# 1-Schematic_monitoring_v0_1.net
KiCad netlist of a schematic drawn in EasyEDA
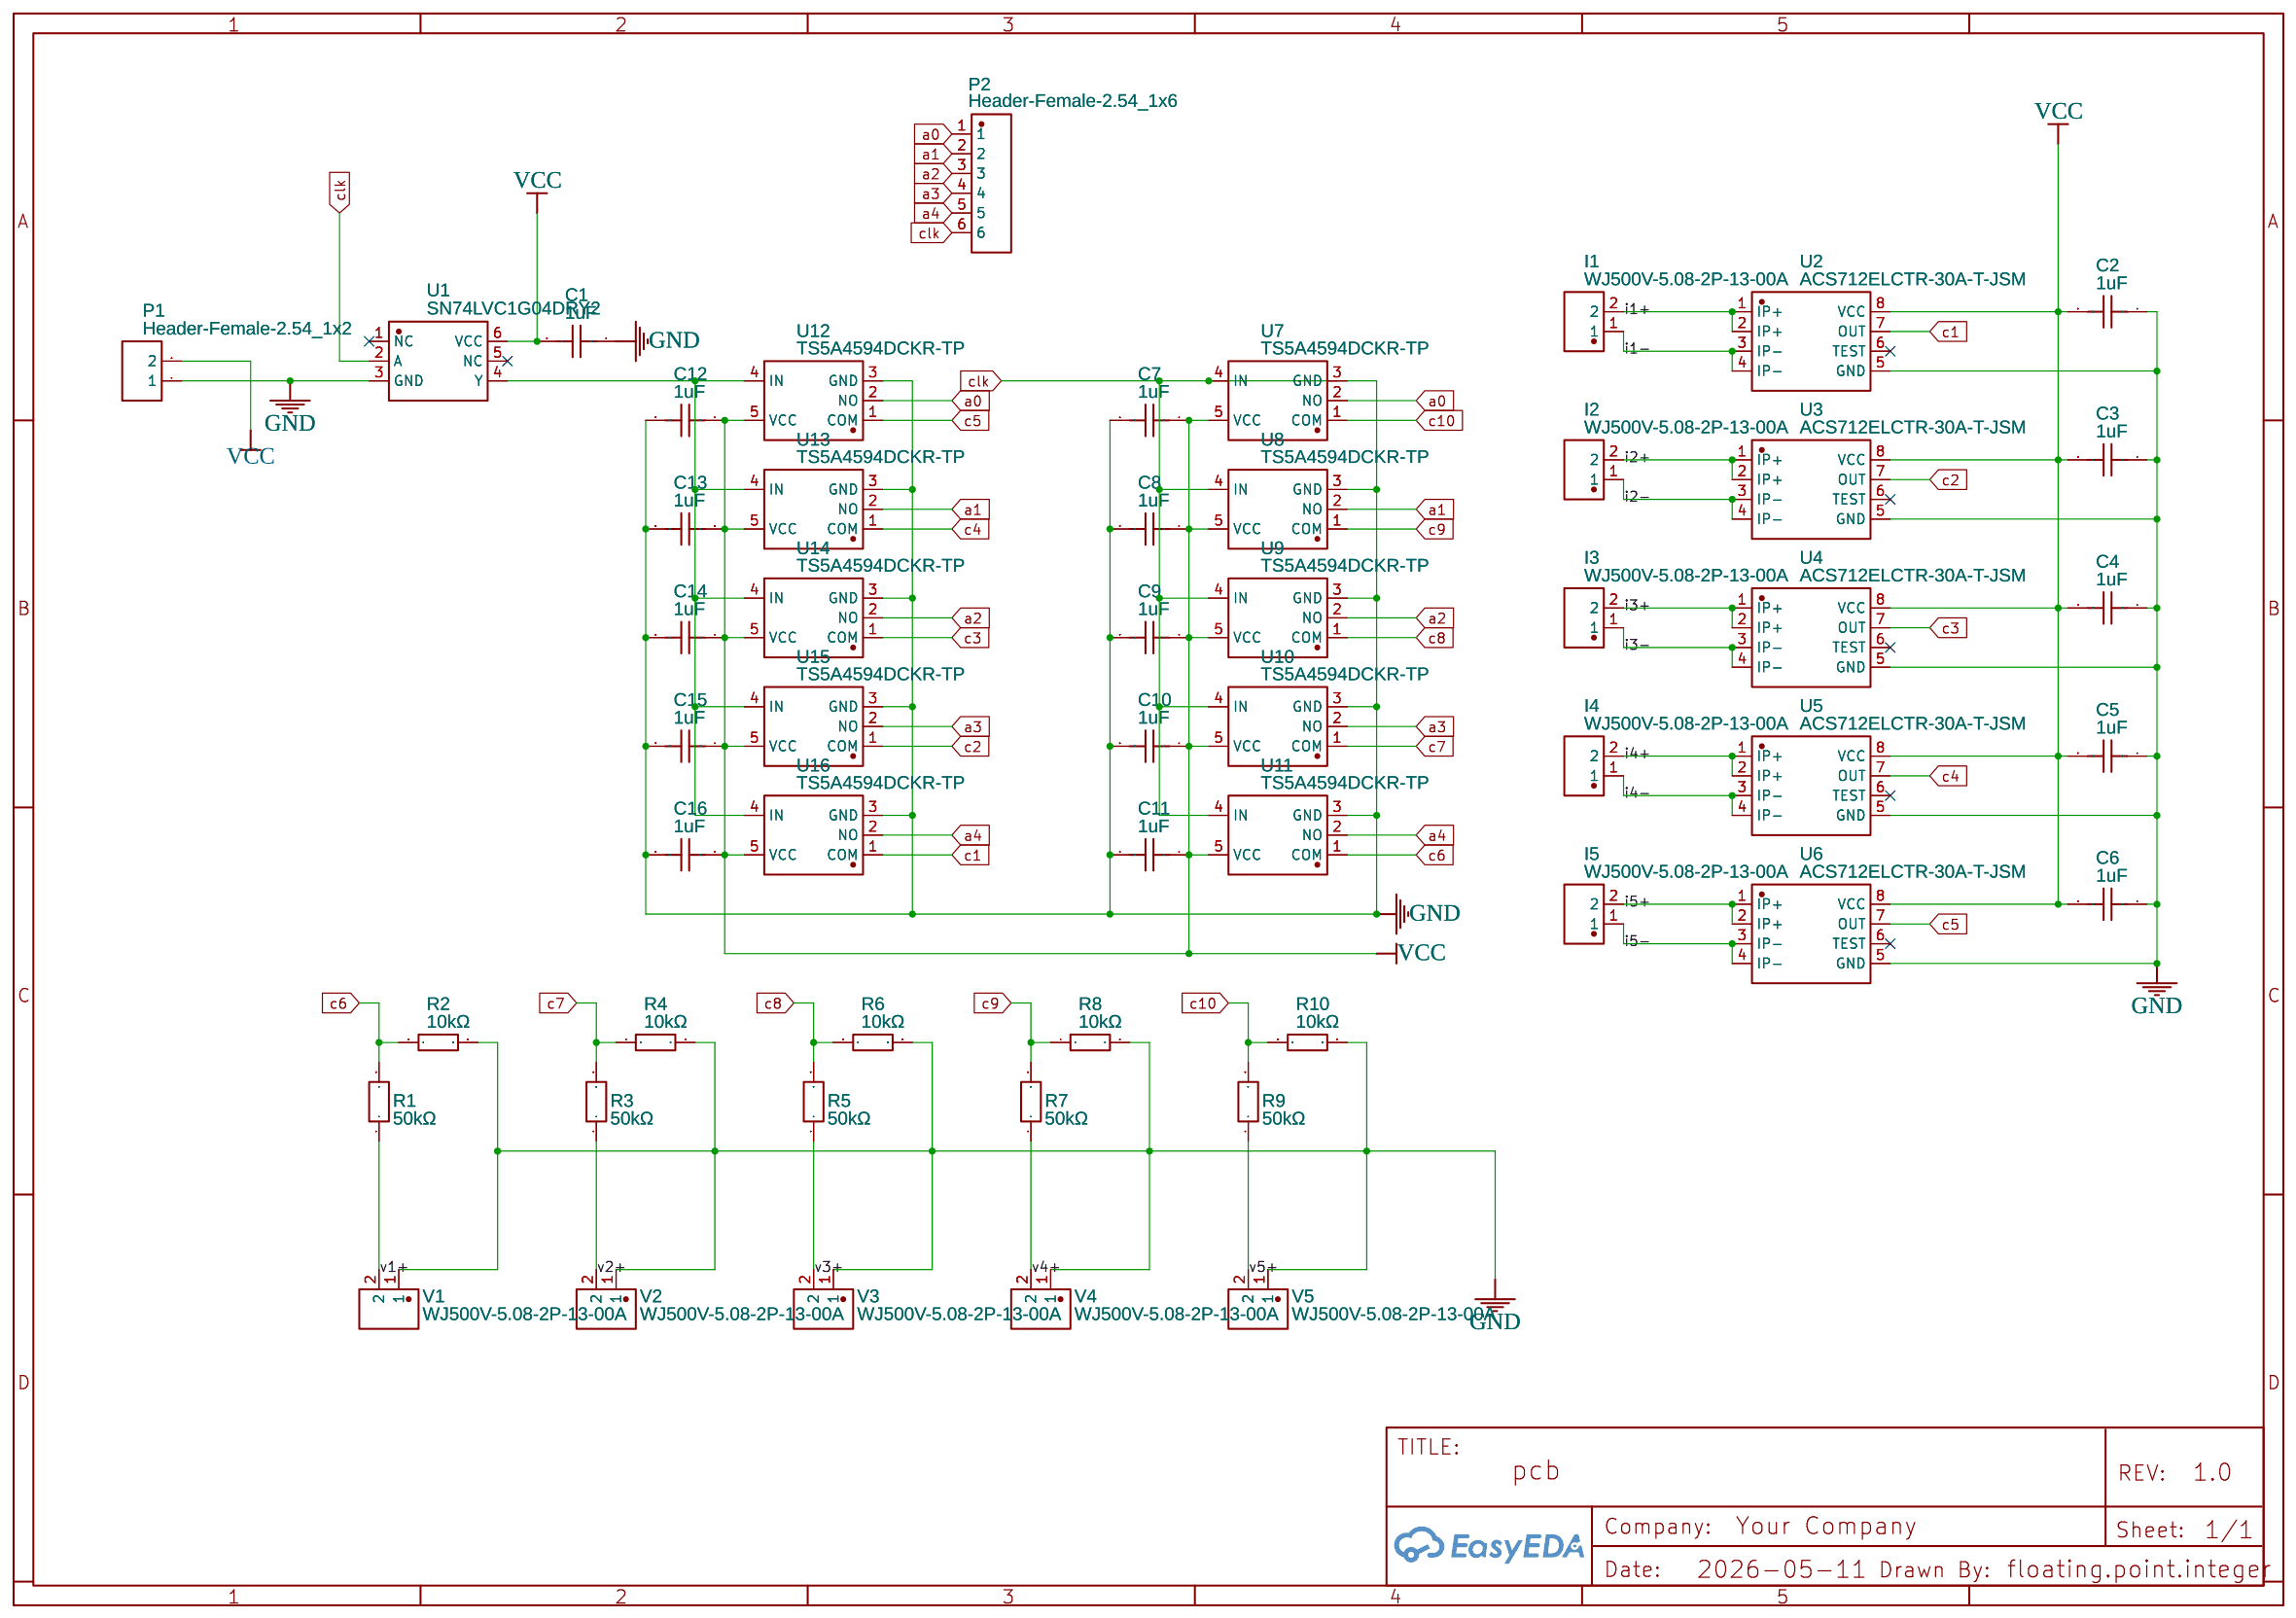
[diagram p0: schematic sheet]

(export (version "E")
  (design (tool "Eeschema 10.0.6"))
  (components
    (comp (ref "C1")
      (value "1uF")
      (fields (field (name "Manufacturer Part") "0603B105K250CT") (field (name "Manufacturer") "Walsin(华新科)"))
      (libsource (lib "") (part "0603B105K250CT"))
    )
    (comp (ref "C2")
      (value "1uF")
      (fields (field (name "Manufacturer Part") "0603B105K250CT") (field (name "Manufacturer") "Walsin(华新科)"))
      (libsource (lib "") (part "0603B105K250CT"))
    )
    (comp (ref "C3")
      (value "1uF")
      (fields (field (name "Manufacturer Part") "0603B105K250CT") (field (name "Manufacturer") "Walsin(华新科)"))
      (libsource (lib "") (part "0603B105K250CT"))
    )
    (comp (ref "C4")
      (value "1uF")
      (fields (field (name "Manufacturer Part") "0603B105K250CT") (field (name "Manufacturer") "Walsin(华新科)"))
      (libsource (lib "") (part "0603B105K250CT"))
    )
    (comp (ref "C5")
      (value "1uF")
      (fields (field (name "Manufacturer Part") "0603B105K250CT") (field (name "Manufacturer") "Walsin(华新科)"))
      (libsource (lib "") (part "0603B105K250CT"))
    )
    (comp (ref "C6")
      (value "1uF")
      (fields (field (name "Manufacturer Part") "0603B105K250CT") (field (name "Manufacturer") "Walsin(华新科)"))
      (libsource (lib "") (part "0603B105K250CT"))
    )
    (comp (ref "C7")
      (value "1uF")
      (fields (field (name "Manufacturer Part") "0603B105K250CT") (field (name "Manufacturer") "Walsin(华新科)"))
      (libsource (lib "") (part "0603B105K250CT"))
    )
    (comp (ref "C8")
      (value "1uF")
      (fields (field (name "Manufacturer Part") "0603B105K250CT") (field (name "Manufacturer") "Walsin(华新科)"))
      (libsource (lib "") (part "0603B105K250CT"))
    )
    (comp (ref "C9")
      (value "1uF")
      (fields (field (name "Manufacturer Part") "0603B105K250CT") (field (name "Manufacturer") "Walsin(华新科)"))
      (libsource (lib "") (part "0603B105K250CT"))
    )
    (comp (ref "C10")
      (value "1uF")
      (fields (field (name "Manufacturer Part") "0603B105K250CT") (field (name "Manufacturer") "Walsin(华新科)"))
      (libsource (lib "") (part "0603B105K250CT"))
    )
    (comp (ref "C11")
      (value "1uF")
      (fields (field (name "Manufacturer Part") "0603B105K250CT") (field (name "Manufacturer") "Walsin(华新科)"))
      (libsource (lib "") (part "0603B105K250CT"))
    )
    (comp (ref "C12")
      (value "1uF")
      (fields (field (name "Manufacturer Part") "0603B105K250CT") (field (name "Manufacturer") "Walsin(华新科)"))
      (libsource (lib "") (part "0603B105K250CT"))
    )
    (comp (ref "C13")
      (value "1uF")
      (fields (field (name "Manufacturer Part") "0603B105K250CT") (field (name "Manufacturer") "Walsin(华新科)"))
      (libsource (lib "") (part "0603B105K250CT"))
    )
    (comp (ref "C14")
      (value "1uF")
      (fields (field (name "Manufacturer Part") "0603B105K250CT") (field (name "Manufacturer") "Walsin(华新科)"))
      (libsource (lib "") (part "0603B105K250CT"))
    )
    (comp (ref "C15")
      (value "1uF")
      (fields (field (name "Manufacturer Part") "0603B105K250CT") (field (name "Manufacturer") "Walsin(华新科)"))
      (libsource (lib "") (part "0603B105K250CT"))
    )
    (comp (ref "C16")
      (value "1uF")
      (fields (field (name "Manufacturer Part") "0603B105K250CT") (field (name "Manufacturer") "Walsin(华新科)"))
      (libsource (lib "") (part "0603B105K250CT"))
    )
    (comp (ref "I1")
      (value "WJ500V-5.08-2P-13-00A")
      (fields
        (field (name "Manufacturer Part") "WJ500V-5.08-02P-13-00A")
        (field (name "Manufacturer") "KANGNEX(康奈克斯电气)")
      )
      (libsource (lib "") (part "WJ500V-5.08-2P-13-00A_1"))
    )
    (comp (ref "I2")
      (value "WJ500V-5.08-2P-13-00A")
      (fields
        (field (name "Manufacturer Part") "WJ500V-5.08-02P-13-00A")
        (field (name "Manufacturer") "KANGNEX(康奈克斯电气)")
      )
      (libsource (lib "") (part "WJ500V-5.08-2P-13-00A_1"))
    )
    (comp (ref "I3")
      (value "WJ500V-5.08-2P-13-00A")
      (fields
        (field (name "Manufacturer Part") "WJ500V-5.08-02P-13-00A")
        (field (name "Manufacturer") "KANGNEX(康奈克斯电气)")
      )
      (libsource (lib "") (part "WJ500V-5.08-2P-13-00A_1"))
    )
    (comp (ref "I4")
      (value "WJ500V-5.08-2P-13-00A")
      (fields
        (field (name "Manufacturer Part") "WJ500V-5.08-02P-13-00A")
        (field (name "Manufacturer") "KANGNEX(康奈克斯电气)")
      )
      (libsource (lib "") (part "WJ500V-5.08-2P-13-00A_1"))
    )
    (comp (ref "I5")
      (value "WJ500V-5.08-2P-13-00A")
      (fields
        (field (name "Manufacturer Part") "WJ500V-5.08-02P-13-00A")
        (field (name "Manufacturer") "KANGNEX(康奈克斯电气)")
      )
      (libsource (lib "") (part "WJ500V-5.08-2P-13-00A_1"))
    )
    (comp (ref "P1")
      (value "Header-Female-2.54_1x2")
      (fields (field (name "Manufacturer Part") "2.54-1*2P母") (field (name "Manufacturer") "BOOMELE(博穆精密)"))
      (libsource (lib "") (part "Header-Female-2.54_1x2"))
    )
    (comp (ref "P2")
      (value "Header-Female-2.54_1x6")
      (fields (field (name "Manufacturer Part") "2.54-1*6P母") (field (name "Manufacturer") "BOOMELE(博穆精密)"))
      (libsource (lib "") (part "Header-Female-2.54_1x6"))
    )
    (comp (ref "R1")
      (value "50kΩ")
      (fields (field (name "Manufacturer Part") "RT0603BRD0750KL") (field (name "Manufacturer") "YAGEO(国巨)"))
      (libsource (lib "") (part "RT0603BRD0750KL"))
    )
    (comp (ref "R2")
      (value "10kΩ")
      (fields (field (name "Manufacturer Part") "RT0603DRD0710KL") (field (name "Manufacturer") "YAGEO(国巨)"))
      (libsource (lib "") (part "RT0603DRD0710KL"))
    )
    (comp (ref "R3")
      (value "50kΩ")
      (fields (field (name "Manufacturer Part") "RT0603BRD0750KL") (field (name "Manufacturer") "YAGEO(国巨)"))
      (libsource (lib "") (part "RT0603BRD0750KL"))
    )
    (comp (ref "R4")
      (value "10kΩ")
      (fields (field (name "Manufacturer Part") "RT0603DRD0710KL") (field (name "Manufacturer") "YAGEO(国巨)"))
      (libsource (lib "") (part "RT0603DRD0710KL"))
    )
    (comp (ref "R5")
      (value "50kΩ")
      (fields (field (name "Manufacturer Part") "RT0603BRD0750KL") (field (name "Manufacturer") "YAGEO(国巨)"))
      (libsource (lib "") (part "RT0603BRD0750KL"))
    )
    (comp (ref "R6")
      (value "10kΩ")
      (fields (field (name "Manufacturer Part") "RT0603DRD0710KL") (field (name "Manufacturer") "YAGEO(国巨)"))
      (libsource (lib "") (part "RT0603DRD0710KL"))
    )
    (comp (ref "R7")
      (value "50kΩ")
      (fields (field (name "Manufacturer Part") "RT0603BRD0750KL") (field (name "Manufacturer") "YAGEO(国巨)"))
      (libsource (lib "") (part "RT0603BRD0750KL"))
    )
    (comp (ref "R8")
      (value "10kΩ")
      (fields (field (name "Manufacturer Part") "RT0603DRD0710KL") (field (name "Manufacturer") "YAGEO(国巨)"))
      (libsource (lib "") (part "RT0603DRD0710KL"))
    )
    (comp (ref "R9")
      (value "50kΩ")
      (fields (field (name "Manufacturer Part") "RT0603BRD0750KL") (field (name "Manufacturer") "YAGEO(国巨)"))
      (libsource (lib "") (part "RT0603BRD0750KL"))
    )
    (comp (ref "R10")
      (value "10kΩ")
      (fields (field (name "Manufacturer Part") "RT0603DRD0710KL") (field (name "Manufacturer") "YAGEO(国巨)"))
      (libsource (lib "") (part "RT0603DRD0710KL"))
    )
    (comp (ref "U1")
      (value "SN74LVC1G04DRY2")
      (fields (field (name "Manufacturer") "TI(德州仪器)"))
      (libsource (lib "") (part "SN74LVC1G04DRY2"))
    )
    (comp (ref "U2")
      (value "ACS712ELCTR-30A-T-JSM")
      (fields (field (name "Manufacturer") "JSMSEMI(杰盛微)"))
      (libsource (lib "") (part "ACS712ELCTR-30A-T-JSM"))
    )
    (comp (ref "U3")
      (value "ACS712ELCTR-30A-T-JSM")
      (fields (field (name "Manufacturer") "JSMSEMI(杰盛微)"))
      (libsource (lib "") (part "ACS712ELCTR-30A-T-JSM"))
    )
    (comp (ref "U4")
      (value "ACS712ELCTR-30A-T-JSM")
      (fields (field (name "Manufacturer") "JSMSEMI(杰盛微)"))
      (libsource (lib "") (part "ACS712ELCTR-30A-T-JSM"))
    )
    (comp (ref "U5")
      (value "ACS712ELCTR-30A-T-JSM")
      (fields (field (name "Manufacturer") "JSMSEMI(杰盛微)"))
      (libsource (lib "") (part "ACS712ELCTR-30A-T-JSM"))
    )
    (comp (ref "U6")
      (value "ACS712ELCTR-30A-T-JSM")
      (fields (field (name "Manufacturer") "JSMSEMI(杰盛微)"))
      (libsource (lib "") (part "ACS712ELCTR-30A-T-JSM"))
    )
    (comp (ref "U7")
      (value "TS5A4594DCKR-TP")
      (fields (field (name "Manufacturer") "TECH PUBLIC(台舟)"))
      (libsource (lib "") (part "TS5A4594DCKR-TP"))
    )
    (comp (ref "U8")
      (value "TS5A4594DCKR-TP")
      (fields (field (name "Manufacturer") "TECH PUBLIC(台舟)"))
      (libsource (lib "") (part "TS5A4594DCKR-TP"))
    )
    (comp (ref "U9")
      (value "TS5A4594DCKR-TP")
      (fields (field (name "Manufacturer") "TECH PUBLIC(台舟)"))
      (libsource (lib "") (part "TS5A4594DCKR-TP"))
    )
    (comp (ref "U10")
      (value "TS5A4594DCKR-TP")
      (fields (field (name "Manufacturer") "TECH PUBLIC(台舟)"))
      (libsource (lib "") (part "TS5A4594DCKR-TP"))
    )
    (comp (ref "U11")
      (value "TS5A4594DCKR-TP")
      (fields (field (name "Manufacturer") "TECH PUBLIC(台舟)"))
      (libsource (lib "") (part "TS5A4594DCKR-TP"))
    )
    (comp (ref "U12")
      (value "TS5A4594DCKR-TP")
      (fields (field (name "Manufacturer") "TECH PUBLIC(台舟)"))
      (libsource (lib "") (part "TS5A4594DCKR-TP"))
    )
    (comp (ref "U13")
      (value "TS5A4594DCKR-TP")
      (fields (field (name "Manufacturer") "TECH PUBLIC(台舟)"))
      (libsource (lib "") (part "TS5A4594DCKR-TP"))
    )
    (comp (ref "U14")
      (value "TS5A4594DCKR-TP")
      (fields (field (name "Manufacturer") "TECH PUBLIC(台舟)"))
      (libsource (lib "") (part "TS5A4594DCKR-TP"))
    )
    (comp (ref "U15")
      (value "TS5A4594DCKR-TP")
      (fields (field (name "Manufacturer") "TECH PUBLIC(台舟)"))
      (libsource (lib "") (part "TS5A4594DCKR-TP"))
    )
    (comp (ref "U16")
      (value "TS5A4594DCKR-TP")
      (fields (field (name "Manufacturer") "TECH PUBLIC(台舟)"))
      (libsource (lib "") (part "TS5A4594DCKR-TP"))
    )
    (comp (ref "V1")
      (value "WJ500V-5.08-2P-13-00A")
      (fields
        (field (name "Manufacturer Part") "WJ500V-5.08-02P-13-00A")
        (field (name "Manufacturer") "KANGNEX(康奈克斯电气)")
      )
      (libsource (lib "") (part "WJ500V-5.08-2P-13-00A"))
    )
    (comp (ref "V2")
      (value "WJ500V-5.08-2P-13-00A")
      (fields
        (field (name "Manufacturer Part") "WJ500V-5.08-02P-13-00A")
        (field (name "Manufacturer") "KANGNEX(康奈克斯电气)")
      )
      (libsource (lib "") (part "WJ500V-5.08-2P-13-00A"))
    )
    (comp (ref "V3")
      (value "WJ500V-5.08-2P-13-00A")
      (fields
        (field (name "Manufacturer Part") "WJ500V-5.08-02P-13-00A")
        (field (name "Manufacturer") "KANGNEX(康奈克斯电气)")
      )
      (libsource (lib "") (part "WJ500V-5.08-2P-13-00A"))
    )
    (comp (ref "V4")
      (value "WJ500V-5.08-2P-13-00A")
      (fields
        (field (name "Manufacturer Part") "WJ500V-5.08-02P-13-00A")
        (field (name "Manufacturer") "KANGNEX(康奈克斯电气)")
      )
      (libsource (lib "") (part "WJ500V-5.08-2P-13-00A"))
    )
    (comp (ref "V5")
      (value "WJ500V-5.08-2P-13-00A")
      (fields
        (field (name "Manufacturer Part") "WJ500V-5.08-02P-13-00A")
        (field (name "Manufacturer") "KANGNEX(康奈克斯电气)")
      )
      (libsource (lib "") (part "WJ500V-5.08-2P-13-00A"))
    )
  )
  (nets
    (net (code "1") (name "/i1+") (class "Default")
      (node (ref "I1") (pin "2") (pinfunction "2_2") (pintype "unspecified"))
      (node (ref "U2") (pin "1") (pinfunction "IP+_1") (pintype "unspecified"))
      (node (ref "U2") (pin "2") (pinfunction "IP+_2") (pintype "unspecified"))
    )
    (net (code "2") (name "/i1-") (class "Default")
      (node (ref "I1") (pin "1") (pinfunction "1_1") (pintype "unspecified"))
      (node (ref "U2") (pin "3") (pinfunction "IP-_3") (pintype "unspecified"))
      (node (ref "U2") (pin "4") (pinfunction "IP-_4") (pintype "unspecified"))
    )
    (net (code "3") (name "/i2+") (class "Default")
      (node (ref "I2") (pin "2") (pinfunction "2_2") (pintype "unspecified"))
      (node (ref "U3") (pin "1") (pinfunction "IP+_1") (pintype "unspecified"))
      (node (ref "U3") (pin "2") (pinfunction "IP+_2") (pintype "unspecified"))
    )
    (net (code "4") (name "/i2-") (class "Default")
      (node (ref "I2") (pin "1") (pinfunction "1_1") (pintype "unspecified"))
      (node (ref "U3") (pin "3") (pinfunction "IP-_3") (pintype "unspecified"))
      (node (ref "U3") (pin "4") (pinfunction "IP-_4") (pintype "unspecified"))
    )
    (net (code "5") (name "/i3+") (class "Default")
      (node (ref "I3") (pin "2") (pinfunction "2_2") (pintype "unspecified"))
      (node (ref "U4") (pin "1") (pinfunction "IP+_1") (pintype "unspecified"))
      (node (ref "U4") (pin "2") (pinfunction "IP+_2") (pintype "unspecified"))
    )
    (net (code "6") (name "/i3-") (class "Default")
      (node (ref "I3") (pin "1") (pinfunction "1_1") (pintype "unspecified"))
      (node (ref "U4") (pin "3") (pinfunction "IP-_3") (pintype "unspecified"))
      (node (ref "U4") (pin "4") (pinfunction "IP-_4") (pintype "unspecified"))
    )
    (net (code "7") (name "/i4+") (class "Default")
      (node (ref "I4") (pin "2") (pinfunction "2_2") (pintype "unspecified"))
      (node (ref "U5") (pin "1") (pinfunction "IP+_1") (pintype "unspecified"))
      (node (ref "U5") (pin "2") (pinfunction "IP+_2") (pintype "unspecified"))
    )
    (net (code "8") (name "/i4-") (class "Default")
      (node (ref "I4") (pin "1") (pinfunction "1_1") (pintype "unspecified"))
      (node (ref "U5") (pin "3") (pinfunction "IP-_3") (pintype "unspecified"))
      (node (ref "U5") (pin "4") (pinfunction "IP-_4") (pintype "unspecified"))
    )
    (net (code "9") (name "/i5+") (class "Default")
      (node (ref "I5") (pin "2") (pinfunction "2_2") (pintype "unspecified"))
      (node (ref "U6") (pin "1") (pinfunction "IP+_1") (pintype "unspecified"))
      (node (ref "U6") (pin "2") (pinfunction "IP+_2") (pintype "unspecified"))
    )
    (net (code "10") (name "/i5-") (class "Default")
      (node (ref "I5") (pin "1") (pinfunction "1_1") (pintype "unspecified"))
      (node (ref "U6") (pin "3") (pinfunction "IP-_3") (pintype "unspecified"))
      (node (ref "U6") (pin "4") (pinfunction "IP-_4") (pintype "unspecified"))
    )
    (net (code "11") (name "/v1+") (class "Default")
      (node (ref "R1") (pin "1") (pinfunction "1_1") (pintype "unspecified"))
      (node (ref "V1") (pin "2") (pinfunction "2_2") (pintype "unspecified"))
    )
    (net (code "12") (name "/v2+") (class "Default")
      (node (ref "R3") (pin "1") (pinfunction "1_1") (pintype "unspecified"))
      (node (ref "V2") (pin "2") (pinfunction "2_2") (pintype "unspecified"))
    )
    (net (code "13") (name "/v3+") (class "Default")
      (node (ref "R5") (pin "1") (pinfunction "1_1") (pintype "unspecified"))
      (node (ref "V3") (pin "2") (pinfunction "2_2") (pintype "unspecified"))
    )
    (net (code "14") (name "/v4+") (class "Default")
      (node (ref "R7") (pin "1") (pinfunction "1_1") (pintype "unspecified"))
      (node (ref "V4") (pin "2") (pinfunction "2_2") (pintype "unspecified"))
    )
    (net (code "15") (name "/v5+") (class "Default")
      (node (ref "R9") (pin "1") (pinfunction "1_1") (pintype "unspecified"))
      (node (ref "V5") (pin "2") (pinfunction "2_2") (pintype "unspecified"))
    )
    (net (code "16") (name "GND") (class "Default")
      (node (ref "C1") (pin "1") (pinfunction "1_1") (pintype "unspecified"))
      (node (ref "C10") (pin "2") (pinfunction "2_2") (pintype "unspecified"))
      (node (ref "C11") (pin "2") (pinfunction "2_2") (pintype "unspecified"))
      (node (ref "C12") (pin "2") (pinfunction "2_2") (pintype "unspecified"))
      (node (ref "C13") (pin "2") (pinfunction "2_2") (pintype "unspecified"))
      (node (ref "C14") (pin "2") (pinfunction "2_2") (pintype "unspecified"))
      (node (ref "C15") (pin "2") (pinfunction "2_2") (pintype "unspecified"))
      (node (ref "C16") (pin "2") (pinfunction "2_2") (pintype "unspecified"))
      (node (ref "C2") (pin "1") (pinfunction "1_1") (pintype "unspecified"))
      (node (ref "C3") (pin "1") (pinfunction "1_1") (pintype "unspecified"))
      (node (ref "C4") (pin "1") (pinfunction "1_1") (pintype "unspecified"))
      (node (ref "C5") (pin "1") (pinfunction "1_1") (pintype "unspecified"))
      (node (ref "C6") (pin "1") (pinfunction "1_1") (pintype "unspecified"))
      (node (ref "C7") (pin "2") (pinfunction "2_2") (pintype "unspecified"))
      (node (ref "C8") (pin "2") (pinfunction "2_2") (pintype "unspecified"))
      (node (ref "C9") (pin "2") (pinfunction "2_2") (pintype "unspecified"))
      (node (ref "P1") (pin "1") (pinfunction "1_1") (pintype "input"))
      (node (ref "R10") (pin "2") (pinfunction "2_2") (pintype "unspecified"))
      (node (ref "R2") (pin "2") (pinfunction "2_2") (pintype "unspecified"))
      (node (ref "R4") (pin "2") (pinfunction "2_2") (pintype "unspecified"))
      (node (ref "R6") (pin "2") (pinfunction "2_2") (pintype "unspecified"))
      (node (ref "R8") (pin "2") (pinfunction "2_2") (pintype "unspecified"))
      (node (ref "U1") (pin "3") (pinfunction "GND_3") (pintype "unspecified"))
      (node (ref "U10") (pin "3") (pinfunction "GND_3") (pintype "unspecified"))
      (node (ref "U11") (pin "3") (pinfunction "GND_3") (pintype "unspecified"))
      (node (ref "U12") (pin "3") (pinfunction "GND_3") (pintype "unspecified"))
      (node (ref "U13") (pin "3") (pinfunction "GND_3") (pintype "unspecified"))
      (node (ref "U14") (pin "3") (pinfunction "GND_3") (pintype "unspecified"))
      (node (ref "U15") (pin "3") (pinfunction "GND_3") (pintype "unspecified"))
      (node (ref "U16") (pin "3") (pinfunction "GND_3") (pintype "unspecified"))
      (node (ref "U2") (pin "5") (pinfunction "GND_5") (pintype "unspecified"))
      (node (ref "U3") (pin "5") (pinfunction "GND_5") (pintype "unspecified"))
      (node (ref "U4") (pin "5") (pinfunction "GND_5") (pintype "unspecified"))
      (node (ref "U5") (pin "5") (pinfunction "GND_5") (pintype "unspecified"))
      (node (ref "U6") (pin "5") (pinfunction "GND_5") (pintype "unspecified"))
      (node (ref "U7") (pin "3") (pinfunction "GND_3") (pintype "unspecified"))
      (node (ref "U8") (pin "3") (pinfunction "GND_3") (pintype "unspecified"))
      (node (ref "U9") (pin "3") (pinfunction "GND_3") (pintype "unspecified"))
      (node (ref "V1") (pin "1") (pinfunction "1_1") (pintype "unspecified"))
      (node (ref "V2") (pin "1") (pinfunction "1_1") (pintype "unspecified"))
      (node (ref "V3") (pin "1") (pinfunction "1_1") (pintype "unspecified"))
      (node (ref "V4") (pin "1") (pinfunction "1_1") (pintype "unspecified"))
      (node (ref "V5") (pin "1") (pinfunction "1_1") (pintype "unspecified"))
    )
    (net (code "17") (name "Net-(U1-Y)") (class "Default")
      (node (ref "U1") (pin "4") (pinfunction "Y_4") (pintype "unspecified"))
      (node (ref "U12") (pin "4") (pinfunction "IN_4") (pintype "unspecified"))
      (node (ref "U13") (pin "4") (pinfunction "IN_4") (pintype "unspecified"))
      (node (ref "U14") (pin "4") (pinfunction "IN_4") (pintype "unspecified"))
      (node (ref "U15") (pin "4") (pinfunction "IN_4") (pintype "unspecified"))
      (node (ref "U16") (pin "4") (pinfunction "IN_4") (pintype "unspecified"))
    )
    (net (code "18") (name "VCC") (class "Default")
      (node (ref "C1") (pin "2") (pinfunction "2_2") (pintype "unspecified"))
      (node (ref "C10") (pin "1") (pinfunction "1_1") (pintype "unspecified"))
      (node (ref "C11") (pin "1") (pinfunction "1_1") (pintype "unspecified"))
      (node (ref "C12") (pin "1") (pinfunction "1_1") (pintype "unspecified"))
      (node (ref "C13") (pin "1") (pinfunction "1_1") (pintype "unspecified"))
      (node (ref "C14") (pin "1") (pinfunction "1_1") (pintype "unspecified"))
      (node (ref "C15") (pin "1") (pinfunction "1_1") (pintype "unspecified"))
      (node (ref "C16") (pin "1") (pinfunction "1_1") (pintype "unspecified"))
      (node (ref "C2") (pin "2") (pinfunction "2_2") (pintype "unspecified"))
      (node (ref "C3") (pin "2") (pinfunction "2_2") (pintype "unspecified"))
      (node (ref "C4") (pin "2") (pinfunction "2_2") (pintype "unspecified"))
      (node (ref "C5") (pin "2") (pinfunction "2_2") (pintype "unspecified"))
      (node (ref "C6") (pin "2") (pinfunction "2_2") (pintype "unspecified"))
      (node (ref "C7") (pin "1") (pinfunction "1_1") (pintype "unspecified"))
      (node (ref "C8") (pin "1") (pinfunction "1_1") (pintype "unspecified"))
      (node (ref "C9") (pin "1") (pinfunction "1_1") (pintype "unspecified"))
      (node (ref "P1") (pin "2") (pinfunction "2_2") (pintype "input"))
      (node (ref "U1") (pin "6") (pinfunction "VCC_6") (pintype "unspecified"))
      (node (ref "U10") (pin "5") (pinfunction "VCC_5") (pintype "unspecified"))
      (node (ref "U11") (pin "5") (pinfunction "VCC_5") (pintype "unspecified"))
      (node (ref "U12") (pin "5") (pinfunction "VCC_5") (pintype "unspecified"))
      (node (ref "U13") (pin "5") (pinfunction "VCC_5") (pintype "unspecified"))
      (node (ref "U14") (pin "5") (pinfunction "VCC_5") (pintype "unspecified"))
      (node (ref "U15") (pin "5") (pinfunction "VCC_5") (pintype "unspecified"))
      (node (ref "U16") (pin "5") (pinfunction "VCC_5") (pintype "unspecified"))
      (node (ref "U2") (pin "8") (pinfunction "VCC_8") (pintype "unspecified"))
      (node (ref "U3") (pin "8") (pinfunction "VCC_8") (pintype "unspecified"))
      (node (ref "U4") (pin "8") (pinfunction "VCC_8") (pintype "unspecified"))
      (node (ref "U5") (pin "8") (pinfunction "VCC_8") (pintype "unspecified"))
      (node (ref "U6") (pin "8") (pinfunction "VCC_8") (pintype "unspecified"))
      (node (ref "U7") (pin "5") (pinfunction "VCC_5") (pintype "unspecified"))
      (node (ref "U8") (pin "5") (pinfunction "VCC_5") (pintype "unspecified"))
      (node (ref "U9") (pin "5") (pinfunction "VCC_5") (pintype "unspecified"))
    )
    (net (code "19") (name "a0") (class "Default")
      (node (ref "P2") (pin "1") (pinfunction "1_1") (pintype "unspecified"))
      (node (ref "U12") (pin "2") (pinfunction "NO_2") (pintype "unspecified"))
      (node (ref "U7") (pin "2") (pinfunction "NO_2") (pintype "unspecified"))
    )
    (net (code "20") (name "a1") (class "Default")
      (node (ref "P2") (pin "2") (pinfunction "2_2") (pintype "unspecified"))
      (node (ref "U13") (pin "2") (pinfunction "NO_2") (pintype "unspecified"))
      (node (ref "U8") (pin "2") (pinfunction "NO_2") (pintype "unspecified"))
    )
    (net (code "21") (name "a2") (class "Default")
      (node (ref "P2") (pin "3") (pinfunction "3_3") (pintype "unspecified"))
      (node (ref "U14") (pin "2") (pinfunction "NO_2") (pintype "unspecified"))
      (node (ref "U9") (pin "2") (pinfunction "NO_2") (pintype "unspecified"))
    )
    (net (code "22") (name "a3") (class "Default")
      (node (ref "P2") (pin "4") (pinfunction "4_4") (pintype "unspecified"))
      (node (ref "U10") (pin "2") (pinfunction "NO_2") (pintype "unspecified"))
      (node (ref "U15") (pin "2") (pinfunction "NO_2") (pintype "unspecified"))
    )
    (net (code "23") (name "a4") (class "Default")
      (node (ref "P2") (pin "5") (pinfunction "5_5") (pintype "unspecified"))
      (node (ref "U11") (pin "2") (pinfunction "NO_2") (pintype "unspecified"))
      (node (ref "U16") (pin "2") (pinfunction "NO_2") (pintype "unspecified"))
    )
    (net (code "24") (name "c1") (class "Default")
      (node (ref "U16") (pin "1") (pinfunction "COM_1") (pintype "unspecified"))
      (node (ref "U2") (pin "7") (pinfunction "OUT_7") (pintype "unspecified"))
    )
    (net (code "25") (name "c2") (class "Default")
      (node (ref "U15") (pin "1") (pinfunction "COM_1") (pintype "unspecified"))
      (node (ref "U3") (pin "7") (pinfunction "OUT_7") (pintype "unspecified"))
    )
    (net (code "26") (name "c3") (class "Default")
      (node (ref "U14") (pin "1") (pinfunction "COM_1") (pintype "unspecified"))
      (node (ref "U4") (pin "7") (pinfunction "OUT_7") (pintype "unspecified"))
    )
    (net (code "27") (name "c4") (class "Default")
      (node (ref "U13") (pin "1") (pinfunction "COM_1") (pintype "unspecified"))
      (node (ref "U5") (pin "7") (pinfunction "OUT_7") (pintype "unspecified"))
    )
    (net (code "28") (name "c5") (class "Default")
      (node (ref "U12") (pin "1") (pinfunction "COM_1") (pintype "unspecified"))
      (node (ref "U6") (pin "7") (pinfunction "OUT_7") (pintype "unspecified"))
    )
    (net (code "29") (name "c6") (class "Default")
      (node (ref "R1") (pin "2") (pinfunction "2_2") (pintype "unspecified"))
      (node (ref "R2") (pin "1") (pinfunction "1_1") (pintype "unspecified"))
      (node (ref "U11") (pin "1") (pinfunction "COM_1") (pintype "unspecified"))
    )
    (net (code "30") (name "c7") (class "Default")
      (node (ref "R3") (pin "2") (pinfunction "2_2") (pintype "unspecified"))
      (node (ref "R4") (pin "1") (pinfunction "1_1") (pintype "unspecified"))
      (node (ref "U10") (pin "1") (pinfunction "COM_1") (pintype "unspecified"))
    )
    (net (code "31") (name "c8") (class "Default")
      (node (ref "R5") (pin "2") (pinfunction "2_2") (pintype "unspecified"))
      (node (ref "R6") (pin "1") (pinfunction "1_1") (pintype "unspecified"))
      (node (ref "U9") (pin "1") (pinfunction "COM_1") (pintype "unspecified"))
    )
    (net (code "32") (name "c9") (class "Default")
      (node (ref "R7") (pin "2") (pinfunction "2_2") (pintype "unspecified"))
      (node (ref "R8") (pin "1") (pinfunction "1_1") (pintype "unspecified"))
      (node (ref "U8") (pin "1") (pinfunction "COM_1") (pintype "unspecified"))
    )
    (net (code "33") (name "c10") (class "Default")
      (node (ref "R10") (pin "1") (pinfunction "1_1") (pintype "unspecified"))
      (node (ref "R9") (pin "2") (pinfunction "2_2") (pintype "unspecified"))
      (node (ref "U7") (pin "1") (pinfunction "COM_1") (pintype "unspecified"))
    )
    (net (code "34") (name "clk") (class "Default")
      (node (ref "P2") (pin "6") (pinfunction "6_6") (pintype "unspecified"))
      (node (ref "U1") (pin "2") (pinfunction "A_2") (pintype "unspecified"))
      (node (ref "U10") (pin "4") (pinfunction "IN_4") (pintype "unspecified"))
      (node (ref "U11") (pin "4") (pinfunction "IN_4") (pintype "unspecified"))
      (node (ref "U7") (pin "4") (pinfunction "IN_4") (pintype "unspecified"))
      (node (ref "U8") (pin "4") (pinfunction "IN_4") (pintype "unspecified"))
      (node (ref "U9") (pin "4") (pinfunction "IN_4") (pintype "unspecified"))
    )
    (net (code "35") (name "unconnected-(U1-NC-Pad1)") (class "Default")
      (node (ref "U1") (pin "1") (pinfunction "NC_1") (pintype "unspecified+no_connect"))
    )
    (net (code "36") (name "unconnected-(U1-NC-Pad5)") (class "Default")
      (node (ref "U1") (pin "5") (pinfunction "NC_5") (pintype "unspecified+no_connect"))
    )
    (net (code "37") (name "unconnected-(U2-TEST-Pad6)") (class "Default")
      (node (ref "U2") (pin "6") (pinfunction "TEST_6") (pintype "unspecified+no_connect"))
    )
    (net (code "38") (name "unconnected-(U3-TEST-Pad6)") (class "Default")
      (node (ref "U3") (pin "6") (pinfunction "TEST_6") (pintype "unspecified+no_connect"))
    )
    (net (code "39") (name "unconnected-(U4-TEST-Pad6)") (class "Default")
      (node (ref "U4") (pin "6") (pinfunction "TEST_6") (pintype "unspecified+no_connect"))
    )
    (net (code "40") (name "unconnected-(U5-TEST-Pad6)") (class "Default")
      (node (ref "U5") (pin "6") (pinfunction "TEST_6") (pintype "unspecified+no_connect"))
    )
    (net (code "41") (name "unconnected-(U6-TEST-Pad6)") (class "Default")
      (node (ref "U6") (pin "6") (pinfunction "TEST_6") (pintype "unspecified+no_connect"))
    )
  )
)
